# FPGA.net
KiCad netlist of a schematic drawn in Altium Designer
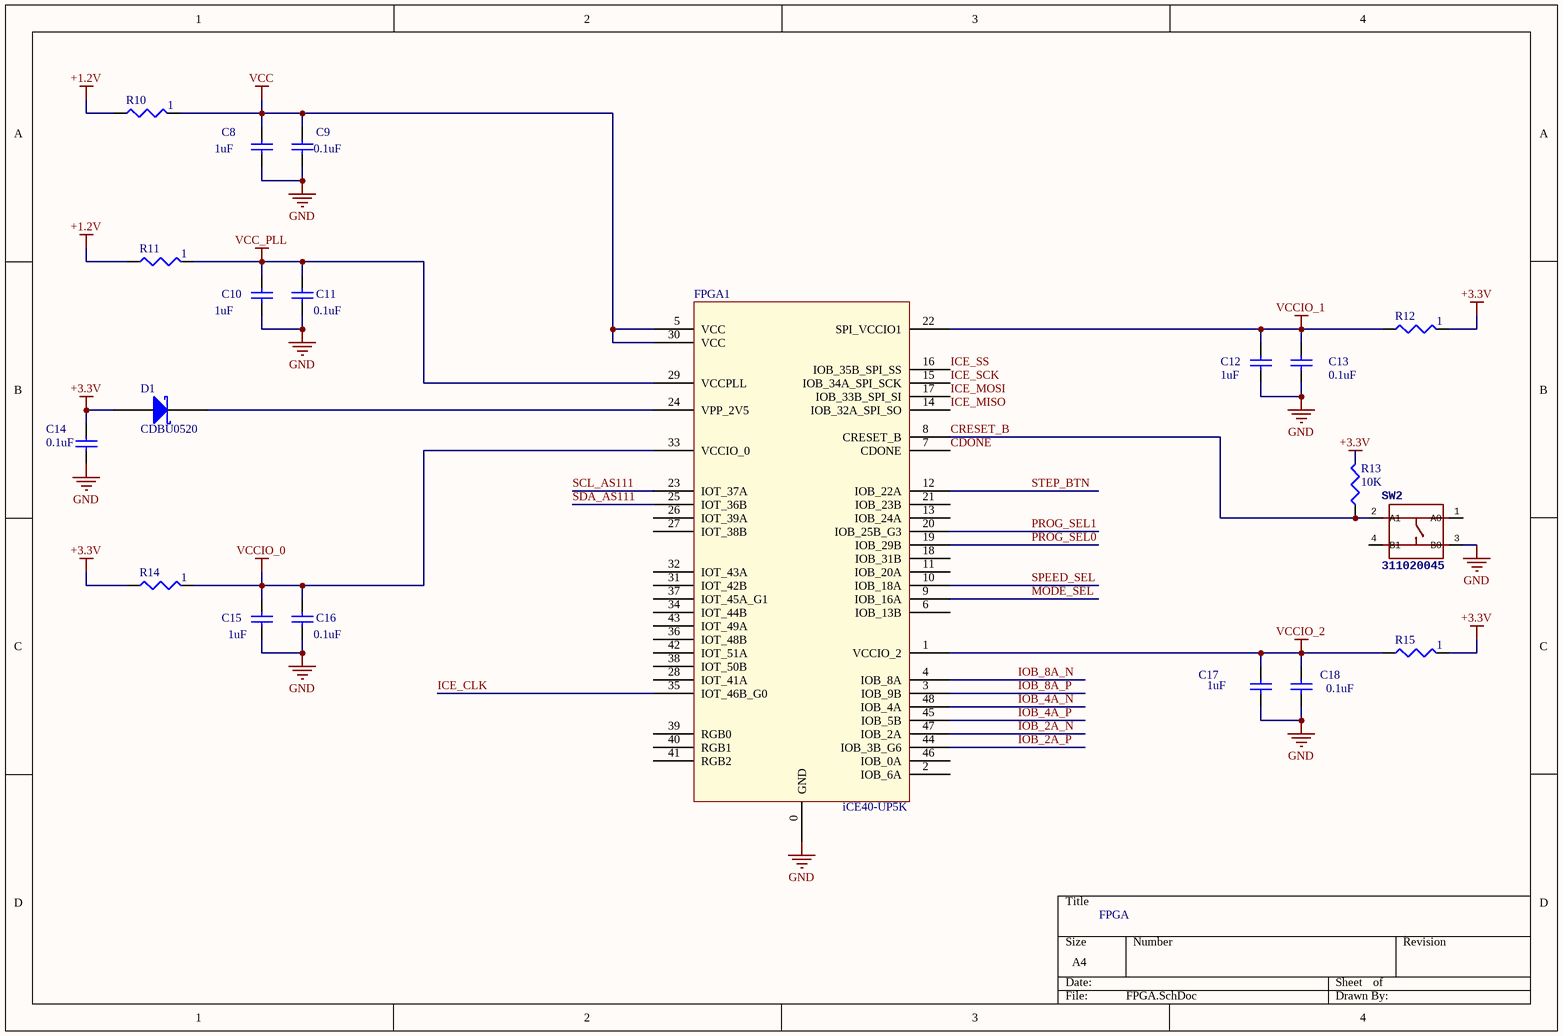
[diagram p0: FPGA.SchDoc]

(export (version "E")
  (design (tool "Eeschema 10.0.6"))
  (components
    (comp (ref "C8")
      (value "1uF")
      (footprint "C0402")
      (description "Capacitor (Semiconductor SIM Model)")
      (fields
        (field (name "MANUFACTURER") "TDK Corporation")
        (field (name "MANUFACTURER PART NUMBER") "CGB2A1JB1E105M033BC")
        (field (name "PUBLISHER") "Altium Limited")
      )
      (libsource (lib "Miscellaneous Devices") (part "Cap Semi"))
    )
    (comp (ref "C9")
      (value "0.1uF")
      (footprint "C0402")
      (description "Capacitor (Semiconductor SIM Model)")
      (fields
        (field (name "MANUFACTURER") "Samsung Electro-Mechanics")
        (field (name "MANUFACTURER PART NUMBER") "CL05B104KA5NNNC")
        (field (name "PUBLISHER") "Altium Limited")
      )
      (libsource (lib "Miscellaneous Devices") (part "Cap Semi"))
    )
    (comp (ref "C10")
      (value "1uF")
      (footprint "C0402")
      (description "Capacitor (Semiconductor SIM Model)")
      (fields
        (field (name "MANUFACTURER") "TDK Corporation")
        (field (name "MANUFACTURER PART NUMBER") "CGB2A1JB1E105M033BC")
        (field (name "PUBLISHER") "Altium Limited")
      )
      (libsource (lib "Miscellaneous Devices") (part "Cap Semi"))
    )
    (comp (ref "C11")
      (value "0.1uF")
      (footprint "C0402")
      (description "Capacitor (Semiconductor SIM Model)")
      (fields
        (field (name "MANUFACTURER") "Samsung Electro-Mechanics")
        (field (name "MANUFACTURER PART NUMBER") "CL05B104KA5NNNC")
        (field (name "PUBLISHER") "Altium Limited")
      )
      (libsource (lib "Miscellaneous Devices") (part "Cap Semi"))
    )
    (comp (ref "C12")
      (value "1uF")
      (footprint "C0402")
      (description "Capacitor (Semiconductor SIM Model)")
      (fields
        (field (name "MANUFACTURER") "TDK Corporation")
        (field (name "MANUFACTURER PART NUMBER") "CGB2A1JB1E105M033BC")
        (field (name "PUBLISHER") "Altium Limited")
      )
      (libsource (lib "Miscellaneous Devices") (part "Cap Semi"))
    )
    (comp (ref "C13")
      (value "0.1uF")
      (footprint "C0402")
      (description "Capacitor (Semiconductor SIM Model)")
      (fields
        (field (name "MANUFACTURER") "Samsung Electro-Mechanics")
        (field (name "MANUFACTURER PART NUMBER") "CL05B104KA5NNNC")
        (field (name "PUBLISHER") "Altium Limited")
      )
      (libsource (lib "Miscellaneous Devices") (part "Cap Semi"))
    )
    (comp (ref "C14")
      (value "0.1uF")
      (footprint "C0402")
      (description "Capacitor (Semiconductor SIM Model)")
      (fields
        (field (name "MANUFACTURER") "Samsung Electro-Mechanics")
        (field (name "MANUFACTURER PART NUMBER") "CL05B104KA5NNNC")
        (field (name "PUBLISHER") "Altium Limited")
      )
      (libsource (lib "Miscellaneous Devices") (part "Cap Semi"))
    )
    (comp (ref "C15")
      (value "1uF")
      (footprint "C0402")
      (description "Capacitor (Semiconductor SIM Model)")
      (fields
        (field (name "MANUFACTURER") "TDK Corporation")
        (field (name "MANUFACTURER PART NUMBER") "CGB2A1JB1E105M033BC")
        (field (name "PUBLISHER") "Altium Limited")
      )
      (libsource (lib "Miscellaneous Devices") (part "Cap Semi"))
    )
    (comp (ref "C16")
      (value "0.1uF")
      (footprint "C0402")
      (description "Capacitor (Semiconductor SIM Model)")
      (fields
        (field (name "MANUFACTURER") "Samsung Electro-Mechanics")
        (field (name "MANUFACTURER PART NUMBER") "CL05B104KA5NNNC")
        (field (name "PUBLISHER") "Altium Limited")
      )
      (libsource (lib "Miscellaneous Devices") (part "Cap Semi"))
    )
    (comp (ref "C17")
      (value "1uF")
      (footprint "C0402")
      (description "Capacitor (Semiconductor SIM Model)")
      (fields
        (field (name "MANUFACTURER") "TDK Corporation")
        (field (name "MANUFACTURER PART NUMBER") "CGB2A1JB1E105M033BC")
        (field (name "PUBLISHER") "Altium Limited")
      )
      (libsource (lib "Miscellaneous Devices") (part "Cap Semi"))
    )
    (comp (ref "C18")
      (value "0.1uF")
      (footprint "C0402")
      (description "Capacitor (Semiconductor SIM Model)")
      (fields
        (field (name "MANUFACTURER") "Samsung Electro-Mechanics")
        (field (name "MANUFACTURER PART NUMBER") "CL05B104KA5NNNC")
        (field (name "PUBLISHER") "Altium Limited")
      )
      (libsource (lib "Miscellaneous Devices") (part "Cap Semi"))
    )
    (comp (ref "D1")
      (value "CDBU0520")
      (footprint "CDBU0520")
      (description "DIODE SCHOTTKY 20V 500MA 0603")
      (fields (field (name "MANUFACTURER") "Comchip Technology"))
      (libsource (lib "FPGAlib") (part "CDBU0520"))
    )
    (comp (ref "FPGA1")
      (value "iCE40-UP5K")
      (footprint "SLAB-QFN48-7X7-MD")
      (description "iCE40-UP5K FPGA")
      (fields
        (field (name "MANUFACTURER") "Lattice Semiconductor Corporation")
        (field (name "MANUFACTURER PART NUMBER") "ICE40UP5K-SG48ITR50")
      )
      (libsource (lib "FPGAlib") (part "iCE40-UP5K FPGA"))
    )
    (comp (ref "R10")
      (value "1")
      (footprint "R0402")
      (description "Resistor")
      (fields
        (field (name "MANUFACTURER") "Yageo")
        (field (name "MANUFACTURER PART NUMBER") "AC0402JR-071RL")
        (field (name "PUBLISHER") "Altium Limited")
      )
      (libsource (lib "Miscellaneous Devices") (part "Res3"))
    )
    (comp (ref "R11")
      (value "1")
      (footprint "R0402")
      (description "Resistor")
      (fields
        (field (name "MANUFACTURER") "Yageo")
        (field (name "MANUFACTURER PART NUMBER") "AC0402JR-071RL")
        (field (name "PUBLISHER") "Altium Limited")
      )
      (libsource (lib "Miscellaneous Devices") (part "Res3"))
    )
    (comp (ref "R12")
      (value "1")
      (footprint "R0402")
      (description "Resistor")
      (fields
        (field (name "MANUFACTURER") "Yageo")
        (field (name "MANUFACTURER PART NUMBER") "AC0402JR-071RL")
        (field (name "PUBLISHER") "Altium Limited")
      )
      (libsource (lib "Miscellaneous Devices") (part "Res3"))
    )
    (comp (ref "R13")
      (value "10K")
      (footprint "R0402")
      (description "Resistor")
      (fields
        (field (name "MANUFACTURER") "Yageo")
        (field (name "MANUFACTURER PART NUMBER") "RC0402JR-0710KP")
        (field (name "PUBLISHER") "Altium Limited")
      )
      (libsource (lib "Miscellaneous Devices") (part "Res3"))
    )
    (comp (ref "R14")
      (value "1")
      (footprint "R0402")
      (description "Resistor")
      (fields
        (field (name "MANUFACTURER") "Yageo")
        (field (name "MANUFACTURER PART NUMBER") "AC0402JR-071RL")
        (field (name "PUBLISHER") "Altium Limited")
      )
      (libsource (lib "Miscellaneous Devices") (part "Res3"))
    )
    (comp (ref "R15")
      (value "1")
      (footprint "R0402")
      (description "Resistor")
      (fields
        (field (name "MANUFACTURER") "Yageo")
        (field (name "MANUFACTURER PART NUMBER") "AC0402JR-071RL")
        (field (name "PUBLISHER") "Altium Limited")
      )
      (libsource (lib "Miscellaneous Devices") (part "Res3"))
    )
    (comp (ref "SW2")
      (value "311020045")
      (footprint "SW4-SMD-4.2X3.2X2.5MM")
      (description "SWITCH TACTILE SPST-NO 0.05A 16V")
      (fields (field (name "MPN") "DHT-4235A") (field (name "MANUFACTURER") "C&K"))
      (libsource (lib "FPGAlib") (part "PTS810 SJM 250 SMTR LFS"))
    )
  )
  (nets
    (net (code "1") (name "+1.2V") (class "Default")
      (node (ref "R10") (pin "1") (pinfunction "1_1") (pintype "passive"))
      (node (ref "R11") (pin "1") (pinfunction "1_1") (pintype "passive"))
    )
    (net (code "2") (name "+3.3V") (class "Default")
      (node (ref "C14") (pin "2") (pinfunction "2_2") (pintype "passive"))
      (node (ref "D1") (pin "1") (pintype "passive"))
      (node (ref "R12") (pin "2") (pinfunction "2_2") (pintype "passive"))
      (node (ref "R13") (pin "2") (pinfunction "2_2") (pintype "passive"))
      (node (ref "R14") (pin "1") (pinfunction "1_1") (pintype "passive"))
      (node (ref "R15") (pin "2") (pinfunction "2_2") (pintype "passive"))
    )
    (net (code "3") (name "/CDONE") (class "Default")
      (node (ref "FPGA1") (pin "7") (pinfunction "CDONE_7") (pintype "passive"))
    )
    (net (code "4") (name "/CRESET_B") (class "Default")
      (node (ref "FPGA1") (pin "8") (pinfunction "CRESET_B_8") (pintype "passive"))
      (node (ref "R13") (pin "1") (pinfunction "1_1") (pintype "passive"))
      (node (ref "SW2") (pin "2") (pinfunction "A1_2") (pintype "passive"))
    )
    (net (code "5") (name "/ICE_CLK") (class "Default")
      (node (ref "FPGA1") (pin "35") (pinfunction "IOT_46B_G0_35") (pintype "passive"))
    )
    (net (code "6") (name "/ICE_MISO") (class "Default")
      (node (ref "FPGA1") (pin "14") (pinfunction "IOB_32A_SPI_SO_14") (pintype "passive"))
    )
    (net (code "7") (name "/ICE_MOSI") (class "Default")
      (node (ref "FPGA1") (pin "17") (pinfunction "IOB_33B_SPI_SI_17") (pintype "passive"))
    )
    (net (code "8") (name "/ICE_SCK") (class "Default")
      (node (ref "FPGA1") (pin "15") (pinfunction "IOB_34A_SPI_SCK_15") (pintype "passive"))
    )
    (net (code "9") (name "/ICE_SS") (class "Default")
      (node (ref "FPGA1") (pin "16") (pinfunction "IOB_35B_SPI_SS_16") (pintype "passive"))
    )
    (net (code "10") (name "/IOB_2A_N") (class "Default")
      (node (ref "FPGA1") (pin "47") (pinfunction "IOB_2A_47") (pintype "passive"))
    )
    (net (code "11") (name "/IOB_2A_P") (class "Default")
      (node (ref "FPGA1") (pin "44") (pinfunction "IOB_3B_G6_44") (pintype "passive"))
    )
    (net (code "12") (name "/IOB_4A_N") (class "Default")
      (node (ref "FPGA1") (pin "48") (pinfunction "IOB_4A_48") (pintype "passive"))
    )
    (net (code "13") (name "/IOB_4A_P") (class "Default")
      (node (ref "FPGA1") (pin "45") (pinfunction "IOB_5B_45") (pintype "passive"))
    )
    (net (code "14") (name "/IOB_8A_N") (class "Default")
      (node (ref "FPGA1") (pin "4") (pinfunction "IOB_8A_4") (pintype "passive"))
    )
    (net (code "15") (name "/IOB_8A_P") (class "Default")
      (node (ref "FPGA1") (pin "3") (pinfunction "IOB_9B_3") (pintype "passive"))
    )
    (net (code "16") (name "/MODE_SEL") (class "Default")
      (node (ref "FPGA1") (pin "9") (pinfunction "IOB_16A_9") (pintype "passive"))
    )
    (net (code "17") (name "/PROG_SEL0") (class "Default")
      (node (ref "FPGA1") (pin "19") (pinfunction "IOB_29B_19") (pintype "passive"))
    )
    (net (code "18") (name "/PROG_SEL1") (class "Default")
      (node (ref "FPGA1") (pin "20") (pinfunction "IOB_25B_G3_20") (pintype "passive"))
    )
    (net (code "19") (name "/SCL_AS111") (class "Default")
      (node (ref "FPGA1") (pin "23") (pinfunction "IOT_37A_23") (pintype "passive"))
    )
    (net (code "20") (name "/SDA_AS111") (class "Default")
      (node (ref "FPGA1") (pin "25") (pinfunction "IOT_36B_25") (pintype "passive"))
    )
    (net (code "21") (name "/SPEED_SEL") (class "Default")
      (node (ref "FPGA1") (pin "10") (pinfunction "IOB_18A_10") (pintype "passive"))
    )
    (net (code "22") (name "/STEP_BTN") (class "Default")
      (node (ref "FPGA1") (pin "12") (pinfunction "IOB_22A_12") (pintype "passive"))
    )
    (net (code "23") (name "GND") (class "Default")
      (node (ref "C10") (pin "1") (pinfunction "1_1") (pintype "passive"))
      (node (ref "C11") (pin "1") (pinfunction "1_1") (pintype "passive"))
      (node (ref "C12") (pin "1") (pinfunction "1_1") (pintype "passive"))
      (node (ref "C13") (pin "1") (pinfunction "1_1") (pintype "passive"))
      (node (ref "C14") (pin "1") (pinfunction "1_1") (pintype "passive"))
      (node (ref "C15") (pin "1") (pinfunction "1_1") (pintype "passive"))
      (node (ref "C16") (pin "1") (pinfunction "1_1") (pintype "passive"))
      (node (ref "C17") (pin "1") (pinfunction "1_1") (pintype "passive"))
      (node (ref "C18") (pin "1") (pinfunction "1_1") (pintype "passive"))
      (node (ref "C8") (pin "1") (pinfunction "1_1") (pintype "passive"))
      (node (ref "C9") (pin "1") (pinfunction "1_1") (pintype "passive"))
      (node (ref "FPGA1") (pin "0") (pinfunction "GND_0") (pintype "passive"))
      (node (ref "SW2") (pin "3") (pinfunction "B0_3") (pintype "passive"))
    )
    (net (code "24") (name "Net-(FPGA1-VPP_2V5)") (class "Default")
      (node (ref "D1") (pin "2") (pintype "passive"))
      (node (ref "FPGA1") (pin "24") (pinfunction "VPP_2V5_24") (pintype "passive"))
    )
    (net (code "25") (name "VCC") (class "Default")
      (node (ref "C8") (pin "2") (pinfunction "2_2") (pintype "passive"))
      (node (ref "C9") (pin "2") (pinfunction "2_2") (pintype "passive"))
      (node (ref "FPGA1") (pin "30") (pinfunction "VCC_30") (pintype "passive"))
      (node (ref "FPGA1") (pin "5") (pinfunction "VCC_5") (pintype "passive"))
      (node (ref "R10") (pin "2") (pinfunction "2_2") (pintype "passive"))
    )
    (net (code "26") (name "VCCIO_0") (class "Default")
      (node (ref "C15") (pin "2") (pinfunction "2_2") (pintype "passive"))
      (node (ref "C16") (pin "2") (pinfunction "2_2") (pintype "passive"))
      (node (ref "FPGA1") (pin "33") (pinfunction "VCCIO_0_33") (pintype "passive"))
      (node (ref "R14") (pin "2") (pinfunction "2_2") (pintype "passive"))
    )
    (net (code "27") (name "VCCIO_1") (class "Default")
      (node (ref "C12") (pin "2") (pinfunction "2_2") (pintype "passive"))
      (node (ref "C13") (pin "2") (pinfunction "2_2") (pintype "passive"))
      (node (ref "FPGA1") (pin "22") (pinfunction "SPI_VCCIO1_22") (pintype "passive"))
      (node (ref "R12") (pin "1") (pinfunction "1_1") (pintype "passive"))
    )
    (net (code "28") (name "VCCIO_2") (class "Default")
      (node (ref "C17") (pin "2") (pinfunction "2_2") (pintype "passive"))
      (node (ref "C18") (pin "2") (pinfunction "2_2") (pintype "passive"))
      (node (ref "FPGA1") (pin "1") (pinfunction "VCCIO_2_1") (pintype "passive"))
      (node (ref "R15") (pin "1") (pinfunction "1_1") (pintype "passive"))
    )
    (net (code "29") (name "VCC_PLL") (class "Default")
      (node (ref "C10") (pin "2") (pinfunction "2_2") (pintype "passive"))
      (node (ref "C11") (pin "2") (pinfunction "2_2") (pintype "passive"))
      (node (ref "FPGA1") (pin "29") (pinfunction "VCCPLL_29") (pintype "passive"))
      (node (ref "R11") (pin "2") (pinfunction "2_2") (pintype "passive"))
    )
    (net (code "30") (name "unconnected-(FPGA1-IOB_0A-Pad46)") (class "Default")
      (node (ref "FPGA1") (pin "46") (pinfunction "IOB_0A_46") (pintype "passive"))
    )
    (net (code "31") (name "unconnected-(FPGA1-IOB_6A-Pad2)") (class "Default")
      (node (ref "FPGA1") (pin "2") (pinfunction "IOB_6A_2") (pintype "passive"))
    )
    (net (code "32") (name "unconnected-(FPGA1-IOB_13B-Pad6)") (class "Default")
      (node (ref "FPGA1") (pin "6") (pinfunction "IOB_13B_6") (pintype "passive"))
    )
    (net (code "33") (name "unconnected-(FPGA1-IOB_20A-Pad11)") (class "Default")
      (node (ref "FPGA1") (pin "11") (pinfunction "IOB_20A_11") (pintype "passive"))
    )
    (net (code "34") (name "unconnected-(FPGA1-IOB_23B-Pad21)") (class "Default")
      (node (ref "FPGA1") (pin "21") (pinfunction "IOB_23B_21") (pintype "passive"))
    )
    (net (code "35") (name "unconnected-(FPGA1-IOB_24A-Pad13)") (class "Default")
      (node (ref "FPGA1") (pin "13") (pinfunction "IOB_24A_13") (pintype "passive"))
    )
    (net (code "36") (name "unconnected-(FPGA1-IOB_31B-Pad18)") (class "Default")
      (node (ref "FPGA1") (pin "18") (pinfunction "IOB_31B_18") (pintype "passive"))
    )
    (net (code "37") (name "unconnected-(FPGA1-IOT_38B-Pad27)") (class "Default")
      (node (ref "FPGA1") (pin "27") (pinfunction "IOT_38B_27") (pintype "passive"))
    )
    (net (code "38") (name "unconnected-(FPGA1-IOT_39A-Pad26)") (class "Default")
      (node (ref "FPGA1") (pin "26") (pinfunction "IOT_39A_26") (pintype "passive"))
    )
    (net (code "39") (name "unconnected-(FPGA1-IOT_41A-Pad28)") (class "Default")
      (node (ref "FPGA1") (pin "28") (pinfunction "IOT_41A_28") (pintype "passive"))
    )
    (net (code "40") (name "unconnected-(FPGA1-IOT_42B-Pad31)") (class "Default")
      (node (ref "FPGA1") (pin "31") (pinfunction "IOT_42B_31") (pintype "passive"))
    )
    (net (code "41") (name "unconnected-(FPGA1-IOT_43A-Pad32)") (class "Default")
      (node (ref "FPGA1") (pin "32") (pinfunction "IOT_43A_32") (pintype "passive"))
    )
    (net (code "42") (name "unconnected-(FPGA1-IOT_44B-Pad34)") (class "Default")
      (node (ref "FPGA1") (pin "34") (pinfunction "IOT_44B_34") (pintype "passive"))
    )
    (net (code "43") (name "unconnected-(FPGA1-IOT_45A_G1-Pad37)") (class "Default")
      (node (ref "FPGA1") (pin "37") (pinfunction "IOT_45A_G1_37") (pintype "passive"))
    )
    (net (code "44") (name "unconnected-(FPGA1-IOT_48B-Pad36)") (class "Default")
      (node (ref "FPGA1") (pin "36") (pinfunction "IOT_48B_36") (pintype "passive"))
    )
    (net (code "45") (name "unconnected-(FPGA1-IOT_49A-Pad43)") (class "Default")
      (node (ref "FPGA1") (pin "43") (pinfunction "IOT_49A_43") (pintype "passive"))
    )
    (net (code "46") (name "unconnected-(FPGA1-IOT_50B-Pad38)") (class "Default")
      (node (ref "FPGA1") (pin "38") (pinfunction "IOT_50B_38") (pintype "passive"))
    )
    (net (code "47") (name "unconnected-(FPGA1-IOT_51A-Pad42)") (class "Default")
      (node (ref "FPGA1") (pin "42") (pinfunction "IOT_51A_42") (pintype "passive"))
    )
    (net (code "48") (name "unconnected-(FPGA1-RGB0-Pad39)") (class "Default")
      (node (ref "FPGA1") (pin "39") (pinfunction "RGB0_39") (pintype "passive"))
    )
    (net (code "49") (name "unconnected-(FPGA1-RGB1-Pad40)") (class "Default")
      (node (ref "FPGA1") (pin "40") (pinfunction "RGB1_40") (pintype "passive"))
    )
    (net (code "50") (name "unconnected-(FPGA1-RGB2-Pad41)") (class "Default")
      (node (ref "FPGA1") (pin "41") (pinfunction "RGB2_41") (pintype "passive"))
    )
    (net (code "51") (name "unconnected-(SW2-A0-Pad1)") (class "Default")
      (node (ref "SW2") (pin "1") (pinfunction "A0_1") (pintype "passive"))
    )
    (net (code "52") (name "unconnected-(SW2-B1-Pad4)") (class "Default")
      (node (ref "SW2") (pin "4") (pinfunction "B1_4") (pintype "passive"))
    )
  )
)
